# uc4h_cube_carrier_v0310r-imx.net
KiCad netlist of a schematic drawn in EAGLE
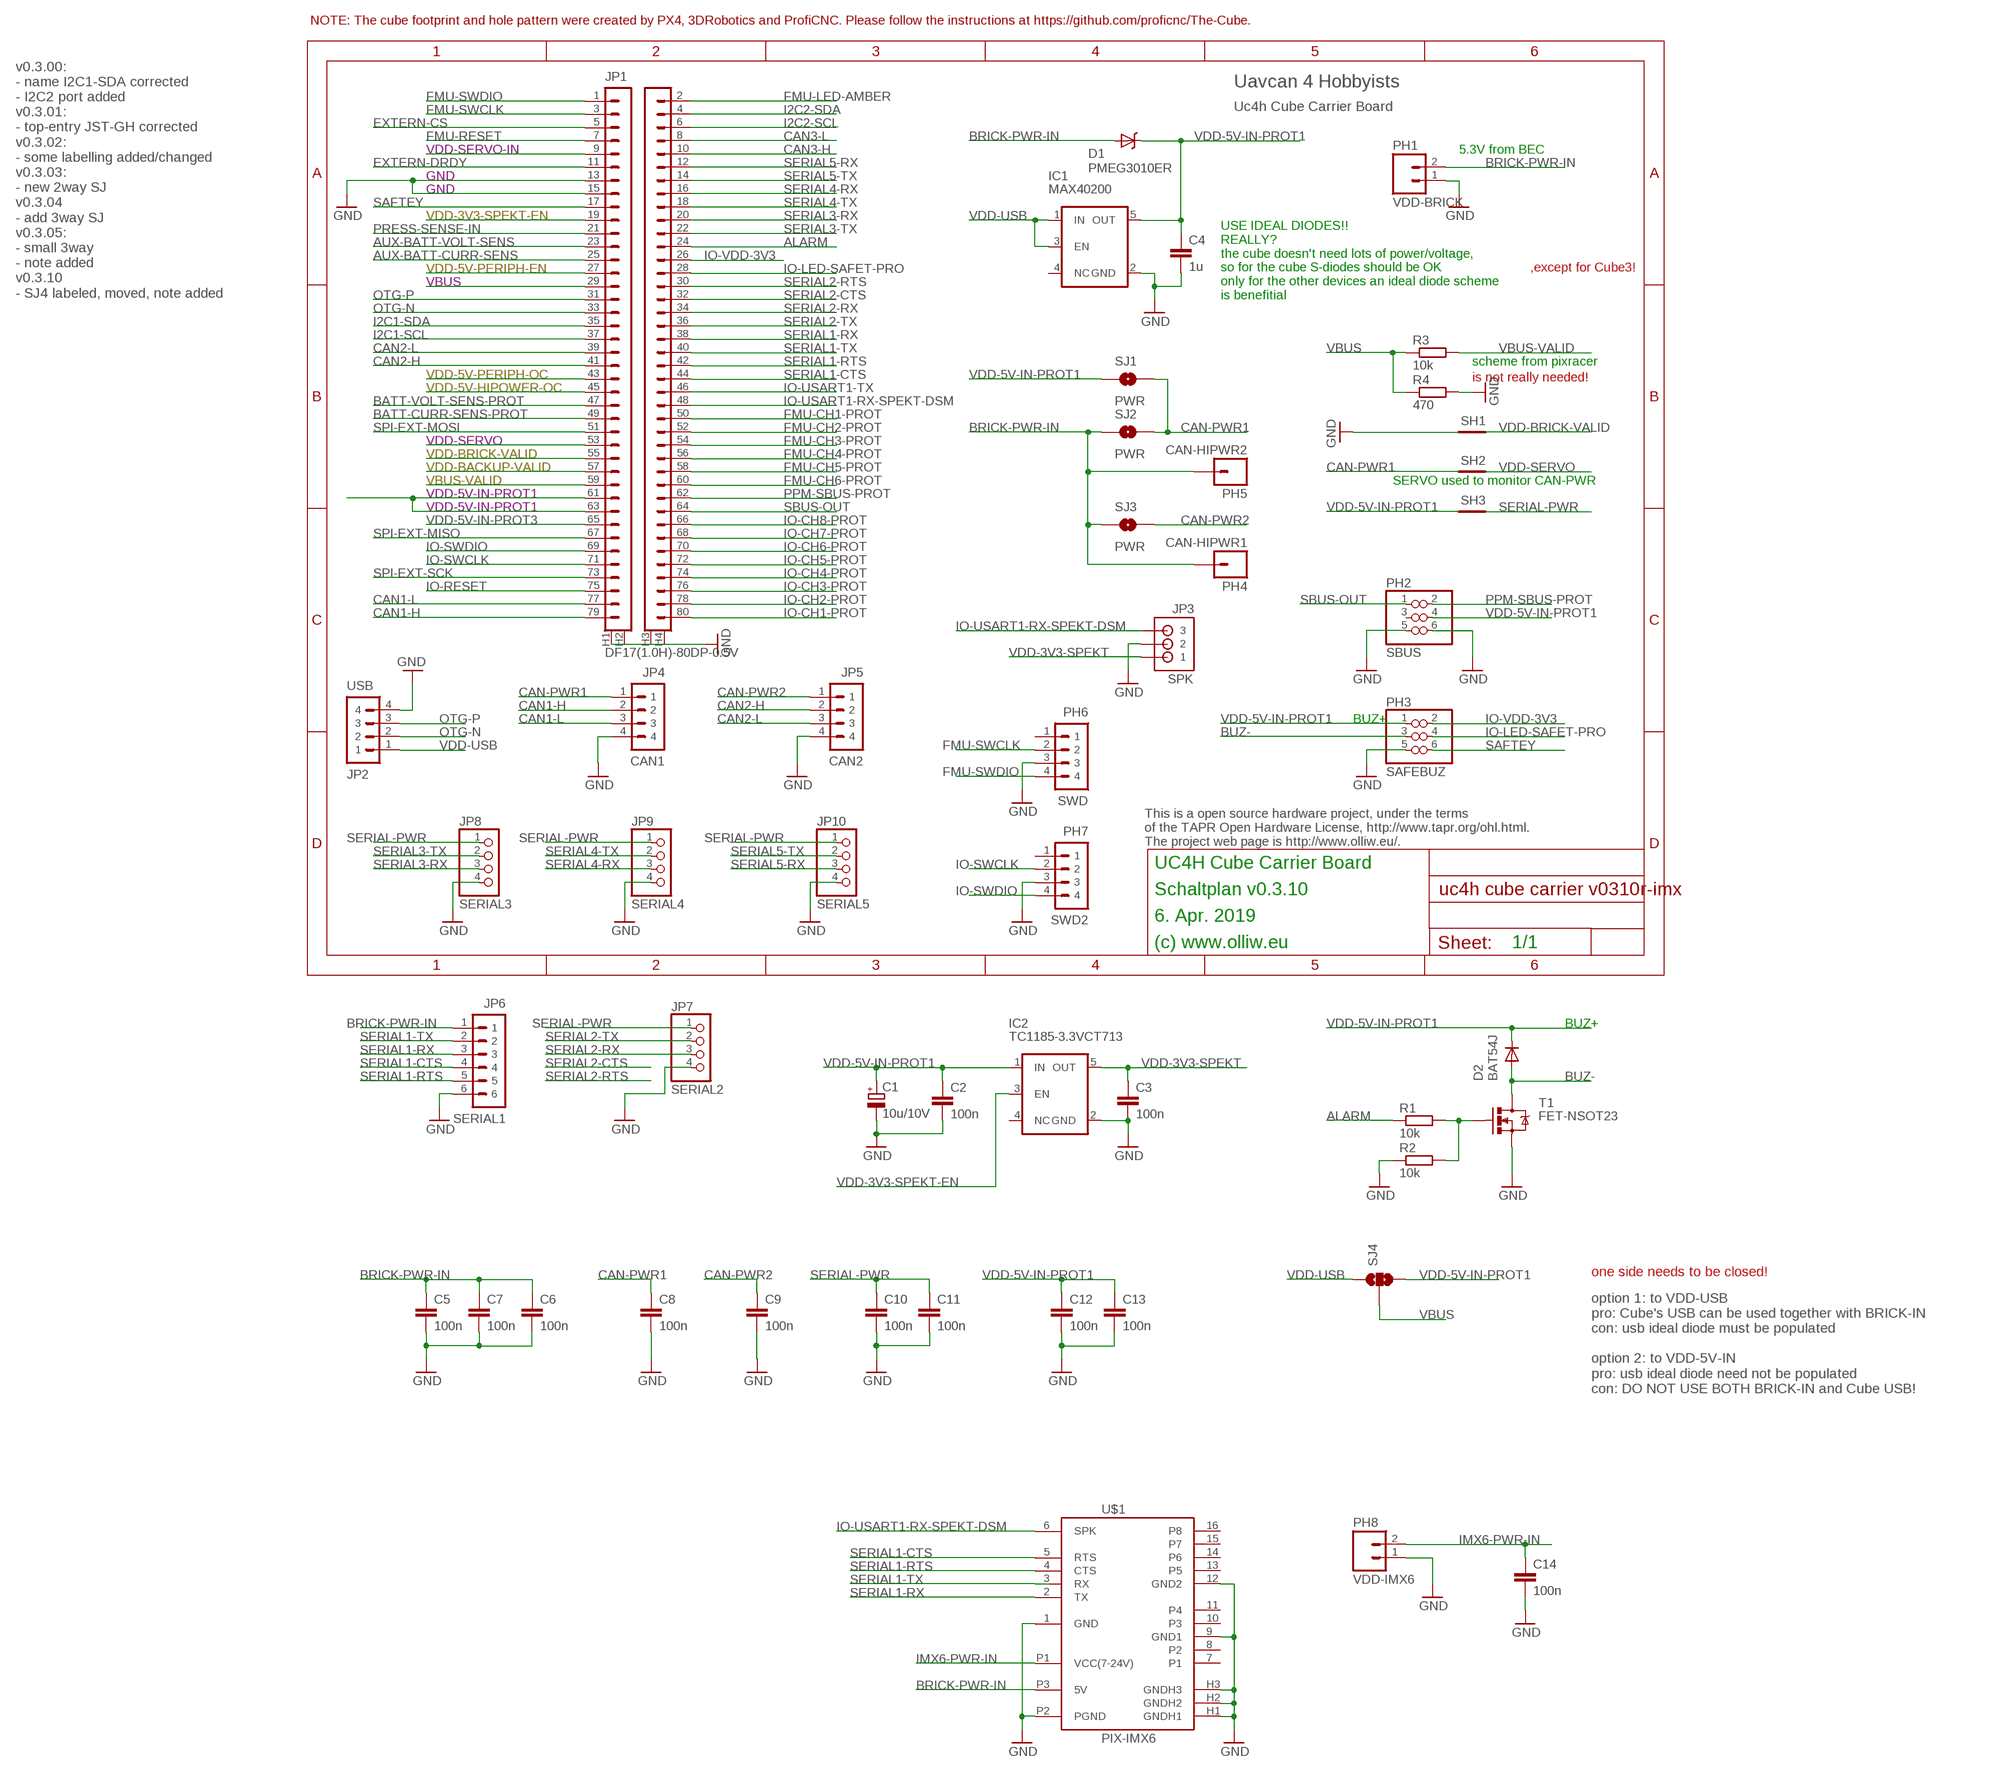
[diagram p0: schematic, sheet 1]

(export (version "E")
  (design (tool "Eeschema 10.0.6"))
  (components
    (comp (ref "C1")
      (value "10u/10V")
      (footprint "eagle-import:SMC_A")
      (libsource (lib "eagle-import") (part "CPOL-EUSMCA"))
    )
    (comp (ref "C2")
      (value "100n")
      (footprint "eagle-import:C0603")
      (libsource (lib "eagle-import") (part "C-EUC0603"))
    )
    (comp (ref "C3")
      (value "100n")
      (footprint "eagle-import:C0603")
      (libsource (lib "eagle-import") (part "C-EUC0603"))
    )
    (comp (ref "C4")
      (value "1u")
      (footprint "eagle-import:C0603")
      (libsource (lib "eagle-import") (part "C-EUC0603"))
    )
    (comp (ref "C5")
      (value "100n")
      (footprint "eagle-import:C0603")
      (libsource (lib "eagle-import") (part "C-EUC0603"))
    )
    (comp (ref "C6")
      (value "100n")
      (footprint "eagle-import:C0603")
      (libsource (lib "eagle-import") (part "C-EUC0603"))
    )
    (comp (ref "C7")
      (value "100n")
      (footprint "eagle-import:C0402")
      (libsource (lib "eagle-import") (part "C-EUC0402"))
    )
    (comp (ref "C8")
      (value "100n")
      (footprint "eagle-import:C0603")
      (libsource (lib "eagle-import") (part "C-EUC0603"))
    )
    (comp (ref "C9")
      (value "100n")
      (footprint "eagle-import:C0603")
      (libsource (lib "eagle-import") (part "C-EUC0603"))
    )
    (comp (ref "C10")
      (value "100n")
      (footprint "eagle-import:C0603")
      (libsource (lib "eagle-import") (part "C-EUC0603"))
    )
    (comp (ref "C11")
      (value "100n")
      (footprint "eagle-import:C0603")
      (libsource (lib "eagle-import") (part "C-EUC0603"))
    )
    (comp (ref "C12")
      (value "100n")
      (footprint "eagle-import:C0603")
      (libsource (lib "eagle-import") (part "C-EUC0603"))
    )
    (comp (ref "C13")
      (value "100n")
      (footprint "eagle-import:C0603")
      (libsource (lib "eagle-import") (part "C-EUC0603"))
    )
    (comp (ref "C14")
      (value "100n")
      (footprint "eagle-import:C0603")
      (libsource (lib "eagle-import") (part "C-EUC0603"))
    )
    (comp (ref "D1")
      (value "PMEG3010ER")
      (footprint "eagle-import:SOD123W-DIODE")
      (libsource (lib "eagle-import") (part "DIODE-SCHOTTKYSOD123-W"))
    )
    (comp (ref "D2")
      (value "BAT54J")
      (footprint "eagle-import:SOD110-R")
      (libsource (lib "eagle-import") (part "DIODE-SOD110-R"))
    )
    (comp (ref "IC1")
      (value "MAX40200")
      (footprint "eagle-import:SOT23-5")
      (libsource (lib "eagle-import") (part "V_REG_TPS76433SOT23-5"))
    )
    (comp (ref "IC2")
      (value "TC1185-3.3VCT713")
      (footprint "eagle-import:SOT23-5")
      (libsource (lib "eagle-import") (part "V_REG_TPS76433SOT23-5"))
    )
    (comp (ref "JP1")
      (value "DF17(1.0H)-80DP-0.5V")
      (footprint "eagle-import:PIX-CUBE-DF17(1.0H)-80DP-0.5V-VIA")
      (libsource (lib "eagle-import") (part "PIX-CUBE-VIA"))
    )
    (comp (ref "JP2")
      (value "USB")
      (footprint "eagle-import:BM04B-GHS-TBT")
      (libsource (lib "eagle-import") (part "JST-GH-4TOP-ENTRY"))
    )
    (comp (ref "JP3")
      (value "SPK")
      (footprint "eagle-import:B3B-ZR")
      (libsource (lib "eagle-import") (part "B3B-ZR"))
    )
    (comp (ref "JP4")
      (value "CAN1")
      (footprint "eagle-import:BM04B-GHS-TBT")
      (libsource (lib "eagle-import") (part "JST-GH-4TOP-ENTRY"))
    )
    (comp (ref "JP5")
      (value "CAN2")
      (footprint "eagle-import:BM04B-GHS-TBT")
      (libsource (lib "eagle-import") (part "JST-GH-4TOP-ENTRY"))
    )
    (comp (ref "JP6")
      (value "SERIAL1")
      (footprint "eagle-import:BM06B-GHS-TBT")
      (libsource (lib "eagle-import") (part "JST-GH-6TOP-ENTRY"))
    )
    (comp (ref "JP7")
      (value "SERIAL2")
      (footprint "eagle-import:PINHEAD_4X1")
      (libsource (lib "eagle-import") (part "PINHEAD_4X1"))
    )
    (comp (ref "JP8")
      (value "SERIAL3")
      (footprint "eagle-import:PINHEAD_4X1")
      (libsource (lib "eagle-import") (part "PINHEAD_4X1"))
    )
    (comp (ref "JP9")
      (value "SERIAL4")
      (footprint "eagle-import:PINHEAD_4X1")
      (libsource (lib "eagle-import") (part "PINHEAD_4X1"))
    )
    (comp (ref "JP10")
      (value "SERIAL5")
      (footprint "eagle-import:PINHEAD_4X1")
      (libsource (lib "eagle-import") (part "PINHEAD_4X1"))
    )
    (comp (ref "PH1")
      (value "VDD-BRICK")
      (footprint "eagle-import:1X02")
      (libsource (lib "eagle-import") (part "M02PTH"))
    )
    (comp (ref "PH2")
      (value "SBUS")
      (footprint "eagle-import:PINHEAD_3X2")
      (libsource (lib "eagle-import") (part "PINHEAD_3X2"))
    )
    (comp (ref "PH3")
      (value "SAFEBUZ")
      (footprint "eagle-import:PINHEAD_3X2")
      (libsource (lib "eagle-import") (part "PINHEAD_3X2"))
    )
    (comp (ref "PH4")
      (value "CAN-HIPWR1")
      (footprint "eagle-import:1X01")
      (libsource (lib "eagle-import") (part "M01PTH"))
    )
    (comp (ref "PH5")
      (value "CAN-HIPWR2")
      (footprint "eagle-import:1X01")
      (libsource (lib "eagle-import") (part "M01PTH"))
    )
    (comp (ref "PH6")
      (value "SWD")
      (footprint "eagle-import:4X1_1P27_OCT_BILEX")
      (libsource (lib "eagle-import") (part "P4X1_1P27-OCT_BILEX"))
    )
    (comp (ref "PH7")
      (value "SWD2")
      (footprint "eagle-import:4X1_1P27_OCT_BILEX")
      (libsource (lib "eagle-import") (part "P4X1_1P27-OCT_BILEX"))
    )
    (comp (ref "PH8")
      (value "VDD-IMX6")
      (footprint "eagle-import:1X02")
      (libsource (lib "eagle-import") (part "M02PTH"))
    )
    (comp (ref "R1")
      (value "10k")
      (footprint "eagle-import:R0402")
      (libsource (lib "eagle-import") (part "R-EU_R0402"))
    )
    (comp (ref "R2")
      (value "10k")
      (footprint "eagle-import:R0402")
      (libsource (lib "eagle-import") (part "R-EU_R0402"))
    )
    (comp (ref "R3")
      (value "10k")
      (footprint "eagle-import:R0402")
      (libsource (lib "eagle-import") (part "R-EU_R0402"))
    )
    (comp (ref "R4")
      (value "470")
      (footprint "eagle-import:R0402")
      (libsource (lib "eagle-import") (part "R-EU_R0402"))
    )
    (comp (ref "SH1")
      (value "SHORT-HT5")
      (footprint "eagle-import:SHORT_TOP-50")
      (libsource (lib "eagle-import") (part "SHORT-HT5"))
    )
    (comp (ref "SH2")
      (value "SHORT-HT5")
      (footprint "eagle-import:SHORT_TOP-50")
      (libsource (lib "eagle-import") (part "SHORT-HT5"))
    )
    (comp (ref "SH3")
      (value "SHORT-HT5")
      (footprint "eagle-import:SHORT_TOP-50")
      (libsource (lib "eagle-import") (part "SHORT-HT5"))
    )
    (comp (ref "SJ1")
      (value "PWR")
      (footprint "eagle-import:SJ-2WAY-BIG-WPASTEC")
      (libsource (lib "eagle-import") (part "SJ-2WAY-WPASTECONNECT"))
    )
    (comp (ref "SJ2")
      (value "PWR")
      (footprint "eagle-import:SJ-2WAY-BIG")
      (libsource (lib "eagle-import") (part "SJ-2WAY-STANDARD"))
    )
    (comp (ref "SJ3")
      (value "PWR")
      (footprint "eagle-import:SJ-2WAY-BIG-WPASTEC")
      (libsource (lib "eagle-import") (part "SJ-2WAY-WPASTECONNECT"))
    )
    (comp (ref "SJ4")
      (value "SJ-3WAY-03")
      (footprint "eagle-import:SJ-3WAY-WPASTEC")
      (libsource (lib "eagle-import") (part "SJ-3WAY-03"))
    )
    (comp (ref "T1")
      (value "FET-NSOT23")
      (footprint "eagle-import:SOT23")
      (libsource (lib "eagle-import") (part "FET-NSOT23"))
    )
    (comp (ref "U$1")
      (value "PIX-IMX6")
      (footprint "eagle-import:PIX-IMX6")
      (libsource (lib "eagle-import") (part "PIX-IMX6"))
    )
  )
  (nets
    (net (code "1") (name "/ALARM") (class "Default")
      (node (ref "JP1") (pin "24") (pinfunction "24_24") (pintype "passive"))
      (node (ref "R1") (pin "1") (pinfunction "1_1") (pintype "passive"))
    )
    (net (code "2") (name "/AUX-BATT-CURR-SENS") (class "Default")
      (node (ref "JP1") (pin "25") (pinfunction "25_25") (pintype "passive"))
    )
    (net (code "3") (name "/AUX-BATT-VOLT-SENS") (class "Default")
      (node (ref "JP1") (pin "23") (pinfunction "23_23") (pintype "passive"))
    )
    (net (code "4") (name "/BATT-CURR-SENS-PROT") (class "Default")
      (node (ref "JP1") (pin "49") (pinfunction "49_49") (pintype "passive"))
    )
    (net (code "5") (name "/BATT-VOLT-SENS-PROT") (class "Default")
      (node (ref "JP1") (pin "47") (pinfunction "47_47") (pintype "passive"))
    )
    (net (code "6") (name "/BRICK-PWR-IN") (class "Default")
      (node (ref "C5") (pin "1") (pinfunction "1_1") (pintype "passive"))
      (node (ref "C6") (pin "1") (pinfunction "1_1") (pintype "passive"))
      (node (ref "C7") (pin "1") (pinfunction "1_1") (pintype "passive"))
      (node (ref "D1") (pin "A") (pinfunction "A_A") (pintype "passive"))
      (node (ref "JP6") (pin "1") (pinfunction "1_1") (pintype "passive"))
      (node (ref "PH1") (pin "2") (pinfunction "2_2") (pintype "passive"))
      (node (ref "PH4") (pin "1") (pinfunction "1_1") (pintype "passive"))
      (node (ref "PH5") (pin "1") (pinfunction "1_1") (pintype "passive"))
      (node (ref "SJ2") (pin "1") (pinfunction "1_1") (pintype "passive"))
      (node (ref "SJ3") (pin "1") (pinfunction "1_1") (pintype "passive"))
      (node (ref "U$1") (pin "P3") (pinfunction "5V_P3") (pintype "power_in"))
    )
    (net (code "7") (name "/BUZ-") (class "Default")
      (node (ref "D2") (pin "A") (pinfunction "A_A") (pintype "passive"))
      (node (ref "PH3") (pin "3") (pinfunction "3_3") (pintype "passive"))
      (node (ref "T1") (pin "3") (pinfunction "D_3") (pintype "passive"))
    )
    (net (code "8") (name "/CAN-PWR1") (class "Default")
      (node (ref "C8") (pin "1") (pinfunction "1_1") (pintype "passive"))
      (node (ref "JP4") (pin "1") (pinfunction "1_1") (pintype "passive"))
      (node (ref "SH2") (pin "1") (pinfunction "P$1_1") (pintype "bidirectional"))
      (node (ref "SJ1") (pin "2") (pinfunction "2_2") (pintype "passive"))
      (node (ref "SJ2") (pin "2") (pinfunction "2_2") (pintype "passive"))
    )
    (net (code "9") (name "/CAN-PWR2") (class "Default")
      (node (ref "C9") (pin "1") (pinfunction "1_1") (pintype "passive"))
      (node (ref "JP5") (pin "1") (pinfunction "1_1") (pintype "passive"))
      (node (ref "SJ3") (pin "2") (pinfunction "2_2") (pintype "passive"))
    )
    (net (code "10") (name "/CAN1-H") (class "Default")
      (node (ref "JP1") (pin "79") (pinfunction "79_79") (pintype "passive"))
      (node (ref "JP4") (pin "2") (pinfunction "2_2") (pintype "passive"))
    )
    (net (code "11") (name "/CAN1-L") (class "Default")
      (node (ref "JP1") (pin "77") (pinfunction "77_77") (pintype "passive"))
      (node (ref "JP4") (pin "3") (pinfunction "3_3") (pintype "passive"))
    )
    (net (code "12") (name "/CAN2-H") (class "Default")
      (node (ref "JP1") (pin "41") (pinfunction "41_41") (pintype "passive"))
      (node (ref "JP5") (pin "2") (pinfunction "2_2") (pintype "passive"))
    )
    (net (code "13") (name "/CAN2-L") (class "Default")
      (node (ref "JP1") (pin "39") (pinfunction "39_39") (pintype "passive"))
      (node (ref "JP5") (pin "3") (pinfunction "3_3") (pintype "passive"))
    )
    (net (code "14") (name "/CAN3-H") (class "Default")
      (node (ref "JP1") (pin "10") (pinfunction "10_10") (pintype "passive"))
    )
    (net (code "15") (name "/CAN3-L") (class "Default")
      (node (ref "JP1") (pin "8") (pinfunction "8_8") (pintype "passive"))
    )
    (net (code "16") (name "/EXTERN-CS") (class "Default")
      (node (ref "JP1") (pin "5") (pinfunction "5_5") (pintype "passive"))
    )
    (net (code "17") (name "/EXTERN-DRDY") (class "Default")
      (node (ref "JP1") (pin "11") (pinfunction "11_11") (pintype "passive"))
    )
    (net (code "18") (name "/FMU-CH1-PROT") (class "Default")
      (node (ref "JP1") (pin "50") (pinfunction "50_50") (pintype "passive"))
    )
    (net (code "19") (name "/FMU-CH2-PROT") (class "Default")
      (node (ref "JP1") (pin "52") (pinfunction "52_52") (pintype "passive"))
    )
    (net (code "20") (name "/FMU-CH3-PROT") (class "Default")
      (node (ref "JP1") (pin "54") (pinfunction "54_54") (pintype "passive"))
    )
    (net (code "21") (name "/FMU-CH4-PROT") (class "Default")
      (node (ref "JP1") (pin "56") (pinfunction "56_56") (pintype "passive"))
    )
    (net (code "22") (name "/FMU-CH5-PROT") (class "Default")
      (node (ref "JP1") (pin "58") (pinfunction "58_58") (pintype "passive"))
    )
    (net (code "23") (name "/FMU-CH6-PROT") (class "Default")
      (node (ref "JP1") (pin "60") (pinfunction "60_60") (pintype "passive"))
    )
    (net (code "24") (name "/FMU-LED-AMBER") (class "Default")
      (node (ref "JP1") (pin "2") (pinfunction "2_2") (pintype "passive"))
    )
    (net (code "25") (name "/FMU-RESET") (class "Default")
      (node (ref "JP1") (pin "7") (pinfunction "7_7") (pintype "passive"))
    )
    (net (code "26") (name "/FMU-SWCLK") (class "Default")
      (node (ref "JP1") (pin "3") (pinfunction "3_3") (pintype "passive"))
      (node (ref "PH6") (pin "2") (pinfunction "2_2") (pintype "passive"))
    )
    (net (code "27") (name "/FMU-SWDIO") (class "Default")
      (node (ref "JP1") (pin "1") (pinfunction "1_1") (pintype "passive"))
      (node (ref "PH6") (pin "4") (pinfunction "4_4") (pintype "passive"))
    )
    (net (code "28") (name "/I2C1-SCL") (class "Default")
      (node (ref "JP1") (pin "37") (pinfunction "37_37") (pintype "passive"))
    )
    (net (code "29") (name "/I2C1-SDA") (class "Default")
      (node (ref "JP1") (pin "35") (pinfunction "35_35") (pintype "passive"))
    )
    (net (code "30") (name "/I2C2-SCL") (class "Default")
      (node (ref "JP1") (pin "6") (pinfunction "6_6") (pintype "passive"))
    )
    (net (code "31") (name "/I2C2-SDA") (class "Default")
      (node (ref "JP1") (pin "4") (pinfunction "4_4") (pintype "passive"))
    )
    (net (code "32") (name "/IMX6-PWR-IN") (class "Default")
      (node (ref "C14") (pin "1") (pinfunction "1_1") (pintype "passive"))
      (node (ref "PH8") (pin "2") (pinfunction "2_2") (pintype "passive"))
      (node (ref "U$1") (pin "P1") (pinfunction "VCC(7-24V)_P1") (pintype "power_in"))
    )
    (net (code "33") (name "/IO-CH1-PROT") (class "Default")
      (node (ref "JP1") (pin "80") (pinfunction "80_80") (pintype "passive"))
    )
    (net (code "34") (name "/IO-CH2-PROT") (class "Default")
      (node (ref "JP1") (pin "78") (pinfunction "78_78") (pintype "passive"))
    )
    (net (code "35") (name "/IO-CH3-PROT") (class "Default")
      (node (ref "JP1") (pin "76") (pinfunction "76_76") (pintype "passive"))
    )
    (net (code "36") (name "/IO-CH4-PROT") (class "Default")
      (node (ref "JP1") (pin "74") (pinfunction "74_74") (pintype "passive"))
    )
    (net (code "37") (name "/IO-CH5-PROT") (class "Default")
      (node (ref "JP1") (pin "72") (pinfunction "72_72") (pintype "passive"))
    )
    (net (code "38") (name "/IO-CH6-PROT") (class "Default")
      (node (ref "JP1") (pin "70") (pinfunction "70_70") (pintype "passive"))
    )
    (net (code "39") (name "/IO-CH7-PROT") (class "Default")
      (node (ref "JP1") (pin "68") (pinfunction "68_68") (pintype "passive"))
    )
    (net (code "40") (name "/IO-CH8-PROT") (class "Default")
      (node (ref "JP1") (pin "66") (pinfunction "66_66") (pintype "passive"))
    )
    (net (code "41") (name "/IO-LED-SAFET-PRO") (class "Default")
      (node (ref "JP1") (pin "28") (pinfunction "28_28") (pintype "passive"))
      (node (ref "PH3") (pin "4") (pinfunction "4_4") (pintype "passive"))
    )
    (net (code "42") (name "/IO-RESET") (class "Default")
      (node (ref "JP1") (pin "75") (pinfunction "75_75") (pintype "passive"))
    )
    (net (code "43") (name "/IO-SWCLK") (class "Default")
      (node (ref "JP1") (pin "71") (pinfunction "71_71") (pintype "passive"))
      (node (ref "PH7") (pin "2") (pinfunction "2_2") (pintype "passive"))
    )
    (net (code "44") (name "/IO-SWDIO") (class "Default")
      (node (ref "JP1") (pin "69") (pinfunction "69_69") (pintype "passive"))
      (node (ref "PH7") (pin "4") (pinfunction "4_4") (pintype "passive"))
    )
    (net (code "45") (name "/IO-USART1-RX-SPEKT-DSM") (class "Default")
      (node (ref "JP1") (pin "48") (pinfunction "48_48") (pintype "passive"))
      (node (ref "JP3") (pin "3") (pinfunction "3_3") (pintype "bidirectional"))
      (node (ref "U$1") (pin "6") (pinfunction "SPK_6") (pintype "bidirectional"))
    )
    (net (code "46") (name "/IO-USART1-TX") (class "Default")
      (node (ref "JP1") (pin "46") (pinfunction "46_46") (pintype "passive"))
    )
    (net (code "47") (name "/IO-VDD-3V3") (class "Default")
      (node (ref "JP1") (pin "26") (pinfunction "26_26") (pintype "passive"))
      (node (ref "PH3") (pin "2") (pinfunction "2_2") (pintype "passive"))
    )
    (net (code "48") (name "/OTG-N") (class "Default")
      (node (ref "JP1") (pin "33") (pinfunction "33_33") (pintype "passive"))
      (node (ref "JP2") (pin "2") (pinfunction "2_2") (pintype "passive"))
    )
    (net (code "49") (name "/OTG-P") (class "Default")
      (node (ref "JP1") (pin "31") (pinfunction "31_31") (pintype "passive"))
      (node (ref "JP2") (pin "3") (pinfunction "3_3") (pintype "passive"))
    )
    (net (code "50") (name "/PPM-SBUS-PROT") (class "Default")
      (node (ref "JP1") (pin "62") (pinfunction "62_62") (pintype "passive"))
      (node (ref "PH2") (pin "2") (pinfunction "2_2") (pintype "passive"))
    )
    (net (code "51") (name "/PRESS-SENSE-IN") (class "Default")
      (node (ref "JP1") (pin "21") (pinfunction "21_21") (pintype "passive"))
    )
    (net (code "52") (name "/SAFTEY") (class "Default")
      (node (ref "JP1") (pin "17") (pinfunction "17_17") (pintype "passive"))
      (node (ref "PH3") (pin "6") (pinfunction "6_6") (pintype "passive"))
    )
    (net (code "53") (name "/SBUS-OUT") (class "Default")
      (node (ref "JP1") (pin "64") (pinfunction "64_64") (pintype "passive"))
      (node (ref "PH2") (pin "1") (pinfunction "1_1") (pintype "passive"))
    )
    (net (code "54") (name "/SERIAL-PWR") (class "Default")
      (node (ref "C10") (pin "1") (pinfunction "1_1") (pintype "passive"))
      (node (ref "C11") (pin "1") (pinfunction "1_1") (pintype "passive"))
      (node (ref "JP10") (pin "1") (pinfunction "1_1") (pintype "passive"))
      (node (ref "JP7") (pin "1") (pinfunction "1_1") (pintype "passive"))
      (node (ref "JP8") (pin "1") (pinfunction "1_1") (pintype "passive"))
      (node (ref "JP9") (pin "1") (pinfunction "1_1") (pintype "passive"))
      (node (ref "SH3") (pin "2") (pinfunction "P$2_2") (pintype "bidirectional"))
    )
    (net (code "55") (name "/SERIAL1-CTS") (class "Default")
      (node (ref "JP1") (pin "44") (pinfunction "44_44") (pintype "passive"))
      (node (ref "JP6") (pin "4") (pinfunction "4_4") (pintype "passive"))
      (node (ref "U$1") (pin "5") (pinfunction "RTS_5") (pintype "bidirectional"))
    )
    (net (code "56") (name "/SERIAL1-RTS") (class "Default")
      (node (ref "JP1") (pin "42") (pinfunction "42_42") (pintype "passive"))
      (node (ref "JP6") (pin "5") (pinfunction "5_5") (pintype "passive"))
      (node (ref "U$1") (pin "4") (pinfunction "CTS_4") (pintype "bidirectional"))
    )
    (net (code "57") (name "/SERIAL1-RX") (class "Default")
      (node (ref "JP1") (pin "38") (pinfunction "38_38") (pintype "passive"))
      (node (ref "JP6") (pin "3") (pinfunction "3_3") (pintype "passive"))
      (node (ref "U$1") (pin "2") (pinfunction "TX_2") (pintype "bidirectional"))
    )
    (net (code "58") (name "/SERIAL1-TX") (class "Default")
      (node (ref "JP1") (pin "40") (pinfunction "40_40") (pintype "passive"))
      (node (ref "JP6") (pin "2") (pinfunction "2_2") (pintype "passive"))
      (node (ref "U$1") (pin "3") (pinfunction "RX_3") (pintype "bidirectional"))
    )
    (net (code "59") (name "/SERIAL2-CTS") (class "Default")
      (node (ref "JP1") (pin "32") (pinfunction "32_32") (pintype "passive"))
    )
    (net (code "60") (name "/SERIAL2-RTS") (class "Default")
      (node (ref "JP1") (pin "30") (pinfunction "30_30") (pintype "passive"))
    )
    (net (code "61") (name "/SERIAL2-RX") (class "Default")
      (node (ref "JP1") (pin "34") (pinfunction "34_34") (pintype "passive"))
      (node (ref "JP7") (pin "3") (pinfunction "3_3") (pintype "passive"))
    )
    (net (code "62") (name "/SERIAL2-TX") (class "Default")
      (node (ref "JP1") (pin "36") (pinfunction "36_36") (pintype "passive"))
      (node (ref "JP7") (pin "2") (pinfunction "2_2") (pintype "passive"))
    )
    (net (code "63") (name "/SERIAL3-RX") (class "Default")
      (node (ref "JP1") (pin "20") (pinfunction "20_20") (pintype "passive"))
      (node (ref "JP8") (pin "3") (pinfunction "3_3") (pintype "passive"))
    )
    (net (code "64") (name "/SERIAL3-TX") (class "Default")
      (node (ref "JP1") (pin "22") (pinfunction "22_22") (pintype "passive"))
      (node (ref "JP8") (pin "2") (pinfunction "2_2") (pintype "passive"))
    )
    (net (code "65") (name "/SERIAL4-RX") (class "Default")
      (node (ref "JP1") (pin "16") (pinfunction "16_16") (pintype "passive"))
      (node (ref "JP9") (pin "3") (pinfunction "3_3") (pintype "passive"))
    )
    (net (code "66") (name "/SERIAL4-TX") (class "Default")
      (node (ref "JP1") (pin "18") (pinfunction "18_18") (pintype "passive"))
      (node (ref "JP9") (pin "2") (pinfunction "2_2") (pintype "passive"))
    )
    (net (code "67") (name "/SERIAL5-RX") (class "Default")
      (node (ref "JP1") (pin "12") (pinfunction "12_12") (pintype "passive"))
      (node (ref "JP10") (pin "3") (pinfunction "3_3") (pintype "passive"))
    )
    (net (code "68") (name "/SERIAL5-TX") (class "Default")
      (node (ref "JP1") (pin "14") (pinfunction "14_14") (pintype "passive"))
      (node (ref "JP10") (pin "2") (pinfunction "2_2") (pintype "passive"))
    )
    (net (code "69") (name "/SPI-EXT-MISO") (class "Default")
      (node (ref "JP1") (pin "67") (pinfunction "67_67") (pintype "passive"))
    )
    (net (code "70") (name "/SPI-EXT-MOSI") (class "Default")
      (node (ref "JP1") (pin "51") (pinfunction "51_51") (pintype "passive"))
    )
    (net (code "71") (name "/SPI-EXT-SCK") (class "Default")
      (node (ref "JP1") (pin "73") (pinfunction "73_73") (pintype "passive"))
    )
    (net (code "72") (name "/VBUS") (class "Default")
      (node (ref "JP1") (pin "29") (pinfunction "29_29") (pintype "passive"))
      (node (ref "R3") (pin "1") (pinfunction "1_1") (pintype "passive"))
      (node (ref "R4") (pin "1") (pinfunction "1_1") (pintype "passive"))
      (node (ref "SJ4") (pin "2") (pinfunction "2_2") (pintype "passive"))
    )
    (net (code "73") (name "/VBUS-VALID") (class "Default")
      (node (ref "JP1") (pin "59") (pinfunction "59_59") (pintype "passive"))
      (node (ref "R3") (pin "2") (pinfunction "2_2") (pintype "passive"))
    )
    (net (code "74") (name "/VDD-3V3-SPEKT") (class "Default")
      (node (ref "C3") (pin "1") (pinfunction "1_1") (pintype "passive"))
      (node (ref "IC2") (pin "5") (pinfunction "OUT_5") (pintype "output"))
      (node (ref "JP3") (pin "1") (pinfunction "1_1") (pintype "bidirectional"))
    )
    (net (code "75") (name "/VDD-3V3-SPEKT-EN") (class "Default")
      (node (ref "IC2") (pin "3") (pinfunction "EN_3") (pintype "input"))
      (node (ref "JP1") (pin "19") (pinfunction "19_19") (pintype "passive"))
    )
    (net (code "76") (name "/VDD-5V-HIPOWER-OC") (class "Default")
      (node (ref "JP1") (pin "45") (pinfunction "45_45") (pintype "passive"))
    )
    (net (code "77") (name "/VDD-5V-IN-PROT1") (class "Default")
      (node (ref "C1") (pin "+") (pinfunction "+_+") (pintype "passive"))
      (node (ref "C12") (pin "1") (pinfunction "1_1") (pintype "passive"))
      (node (ref "C13") (pin "1") (pinfunction "1_1") (pintype "passive"))
      (node (ref "C2") (pin "1") (pinfunction "1_1") (pintype "passive"))
      (node (ref "C4") (pin "1") (pinfunction "1_1") (pintype "passive"))
      (node (ref "D1") (pin "C") (pinfunction "C_C") (pintype "passive"))
      (node (ref "D2") (pin "C") (pinfunction "C_C") (pintype "passive"))
      (node (ref "IC1") (pin "5") (pinfunction "OUT_5") (pintype "output"))
      (node (ref "IC2") (pin "1") (pinfunction "IN_1") (pintype "power_in"))
      (node (ref "JP1") (pin "61") (pinfunction "61_61") (pintype "passive"))
      (node (ref "JP1") (pin "63") (pinfunction "63_63") (pintype "passive"))
      (node (ref "PH2") (pin "4") (pinfunction "4_4") (pintype "passive"))
      (node (ref "PH3") (pin "1") (pinfunction "1_1") (pintype "passive"))
      (node (ref "SH3") (pin "1") (pinfunction "P$1_1") (pintype "bidirectional"))
      (node (ref "SJ1") (pin "1") (pinfunction "1_1") (pintype "passive"))
      (node (ref "SJ4") (pin "3") (pinfunction "3_3") (pintype "passive"))
    )
    (net (code "78") (name "/VDD-5V-IN-PROT3") (class "Default")
      (node (ref "JP1") (pin "65") (pinfunction "65_65") (pintype "passive"))
    )
    (net (code "79") (name "/VDD-5V-PERIPH-EN") (class "Default")
      (node (ref "JP1") (pin "27") (pinfunction "27_27") (pintype "passive"))
    )
    (net (code "80") (name "/VDD-5V-PERIPH-OC") (class "Default")
      (node (ref "JP1") (pin "43") (pinfunction "43_43") (pintype "passive"))
    )
    (net (code "81") (name "/VDD-BACKUP-VALID") (class "Default")
      (node (ref "JP1") (pin "57") (pinfunction "57_57") (pintype "passive"))
    )
    (net (code "82") (name "/VDD-BRICK-VALID") (class "Default")
      (node (ref "JP1") (pin "55") (pinfunction "55_55") (pintype "passive"))
      (node (ref "SH1") (pin "2") (pinfunction "P$2_2") (pintype "bidirectional"))
    )
    (net (code "83") (name "/VDD-SERVO") (class "Default")
      (node (ref "JP1") (pin "53") (pinfunction "53_53") (pintype "passive"))
      (node (ref "SH2") (pin "2") (pinfunction "P$2_2") (pintype "bidirectional"))
    )
    (net (code "84") (name "/VDD-SERVO-IN") (class "Default")
      (node (ref "JP1") (pin "9") (pinfunction "9_9") (pintype "passive"))
    )
    (net (code "85") (name "/VDD-USB") (class "Default")
      (node (ref "IC1") (pin "1") (pinfunction "IN_1") (pintype "power_in"))
      (node (ref "IC1") (pin "3") (pinfunction "EN_3") (pintype "input"))
      (node (ref "JP2") (pin "1") (pinfunction "1_1") (pintype "passive"))
      (node (ref "SJ4") (pin "1") (pinfunction "1_1") (pintype "passive"))
    )
    (net (code "86") (name "GND") (class "Default")
      (node (ref "C1") (pin "-") (pinfunction "-_-") (pintype "passive"))
      (node (ref "C10") (pin "2") (pinfunction "2_2") (pintype "passive"))
      (node (ref "C11") (pin "2") (pinfunction "2_2") (pintype "passive"))
      (node (ref "C12") (pin "2") (pinfunction "2_2") (pintype "passive"))
      (node (ref "C13") (pin "2") (pinfunction "2_2") (pintype "passive"))
      (node (ref "C14") (pin "2") (pinfunction "2_2") (pintype "passive"))
      (node (ref "C2") (pin "2") (pinfunction "2_2") (pintype "passive"))
      (node (ref "C3") (pin "2") (pinfunction "2_2") (pintype "passive"))
      (node (ref "C4") (pin "2") (pinfunction "2_2") (pintype "passive"))
      (node (ref "C5") (pin "2") (pinfunction "2_2") (pintype "passive"))
      (node (ref "C6") (pin "2") (pinfunction "2_2") (pintype "passive"))
      (node (ref "C7") (pin "2") (pinfunction "2_2") (pintype "passive"))
      (node (ref "C8") (pin "2") (pinfunction "2_2") (pintype "passive"))
      (node (ref "C9") (pin "2") (pinfunction "2_2") (pintype "passive"))
      (node (ref "IC1") (pin "2") (pinfunction "GND_2") (pintype "power_in"))
      (node (ref "IC2") (pin "2") (pinfunction "GND_2") (pintype "power_in"))
      (node (ref "JP1") (pin "13") (pinfunction "13_13") (pintype "passive"))
      (node (ref "JP1") (pin "15") (pinfunction "15_15") (pintype "passive"))
      (node (ref "JP1") (pin "H1") (pinfunction "81_H1") (pintype "passive"))
      (node (ref "JP1") (pin "H2") (pinfunction "82_H2") (pintype "passive"))
      (node (ref "JP1") (pin "H3") (pinfunction "83_H3") (pintype "passive"))
      (node (ref "JP1") (pin "H4") (pinfunction "84_H4") (pintype "passive"))
      (node (ref "JP10") (pin "4") (pinfunction "4_4") (pintype "passive"))
      (node (ref "JP2") (pin "4") (pinfunction "4_4") (pintype "passive"))
      (node (ref "JP3") (pin "2") (pinfunction "2_2") (pintype "bidirectional"))
      (node (ref "JP4") (pin "4") (pinfunction "4_4") (pintype "passive"))
      (node (ref "JP5") (pin "4") (pinfunction "4_4") (pintype "passive"))
      (node (ref "JP6") (pin "6") (pinfunction "6_6") (pintype "passive"))
      (node (ref "JP7") (pin "4") (pinfunction "4_4") (pintype "passive"))
      (node (ref "JP8") (pin "4") (pinfunction "4_4") (pintype "passive"))
      (node (ref "JP9") (pin "4") (pinfunction "4_4") (pintype "passive"))
      (node (ref "PH1") (pin "1") (pinfunction "1_1") (pintype "passive"))
      (node (ref "PH2") (pin "5") (pinfunction "5_5") (pintype "passive"))
      (node (ref "PH2") (pin "6") (pinfunction "6_6") (pintype "passive"))
      (node (ref "PH3") (pin "5") (pinfunction "5_5") (pintype "passive"))
      (node (ref "PH6") (pin "3") (pinfunction "3_3") (pintype "passive"))
      (node (ref "PH7") (pin "3") (pinfunction "3_3") (pintype "passive"))
      (node (ref "PH8") (pin "1") (pinfunction "1_1") (pintype "passive"))
      (node (ref "R2") (pin "1") (pinfunction "1_1") (pintype "passive"))
      (node (ref "R4") (pin "2") (pinfunction "2_2") (pintype "passive"))
      (node (ref "SH1") (pin "1") (pinfunction "P$1_1") (pintype "bidirectional"))
      (node (ref "T1") (pin "2") (pinfunction "S_2") (pintype "passive"))
      (node (ref "U$1") (pin "1") (pinfunction "GND_1") (pintype "power_in"))
      (node (ref "U$1") (pin "12") (pinfunction "GND2_12") (pintype "power_in"))
      (node (ref "U$1") (pin "9") (pinfunction "GND1_9") (pintype "power_in"))
      (node (ref "U$1") (pin "H1") (pinfunction "GNDH1_H1") (pintype "power_in"))
      (node (ref "U$1") (pin "H2") (pinfunction "GNDH2_H2") (pintype "power_in"))
      (node (ref "U$1") (pin "H3") (pinfunction "GNDH3_H3") (pintype "power_in"))
      (node (ref "U$1") (pin "P2") (pinfunction "PGND_P2") (pintype "power_in"))
    )
    (net (code "87") (name "Net-(T1-G)") (class "Default")
      (node (ref "R1") (pin "2") (pinfunction "2_2") (pintype "passive"))
      (node (ref "R2") (pin "2") (pinfunction "2_2") (pintype "passive"))
      (node (ref "T1") (pin "1") (pinfunction "G_1") (pintype "passive"))
    )
    (net (code "88") (name "unconnected-(IC1-NC-Pad4)") (class "Default")
      (node (ref "IC1") (pin "4") (pinfunction "NC_4") (pintype "passive"))
    )
    (net (code "89") (name "unconnected-(IC2-NC-Pad4)") (class "Default")
      (node (ref "IC2") (pin "4") (pinfunction "NC_4") (pintype "passive"))
    )
    (net (code "90") (name "unconnected-(PH2-Pad3)") (class "Default")
      (node (ref "PH2") (pin "3") (pinfunction "3_3") (pintype "passive"))
    )
    (net (code "91") (name "unconnected-(PH6-Pad1)") (class "Default")
      (node (ref "PH6") (pin "1") (pinfunction "1_1") (pintype "passive"))
    )
    (net (code "92") (name "unconnected-(PH7-Pad1)") (class "Default")
      (node (ref "PH7") (pin "1") (pinfunction "1_1") (pintype "passive"))
    )
    (net (code "93") (name "unconnected-(U$1-P1-Pad7)") (class "Default")
      (node (ref "U$1") (pin "7") (pinfunction "P1_7") (pintype "bidirectional"))
    )
    (net (code "94") (name "unconnected-(U$1-P2-Pad8)") (class "Default")
      (node (ref "U$1") (pin "8") (pinfunction "P2_8") (pintype "bidirectional"))
    )
    (net (code "95") (name "unconnected-(U$1-P3-Pad10)") (class "Default")
      (node (ref "U$1") (pin "10") (pinfunction "P3_10") (pintype "bidirectional"))
    )
    (net (code "96") (name "unconnected-(U$1-P4-Pad11)") (class "Default")
      (node (ref "U$1") (pin "11") (pinfunction "P4_11") (pintype "bidirectional"))
    )
    (net (code "97") (name "unconnected-(U$1-P5-Pad13)") (class "Default")
      (node (ref "U$1") (pin "13") (pinfunction "P5_13") (pintype "bidirectional"))
    )
    (net (code "98") (name "unconnected-(U$1-P6-Pad14)") (class "Default")
      (node (ref "U$1") (pin "14") (pinfunction "P6_14") (pintype "bidirectional"))
    )
    (net (code "99") (name "unconnected-(U$1-P7-Pad15)") (class "Default")
      (node (ref "U$1") (pin "15") (pinfunction "P7_15") (pintype "bidirectional"))
    )
    (net (code "100") (name "unconnected-(U$1-P8-Pad16)") (class "Default")
      (node (ref "U$1") (pin "16") (pinfunction "P8_16") (pintype "bidirectional"))
    )
  )
)
